# FeatherWing_for_MESH.net
KiCad netlist of a schematic drawn in EAGLE
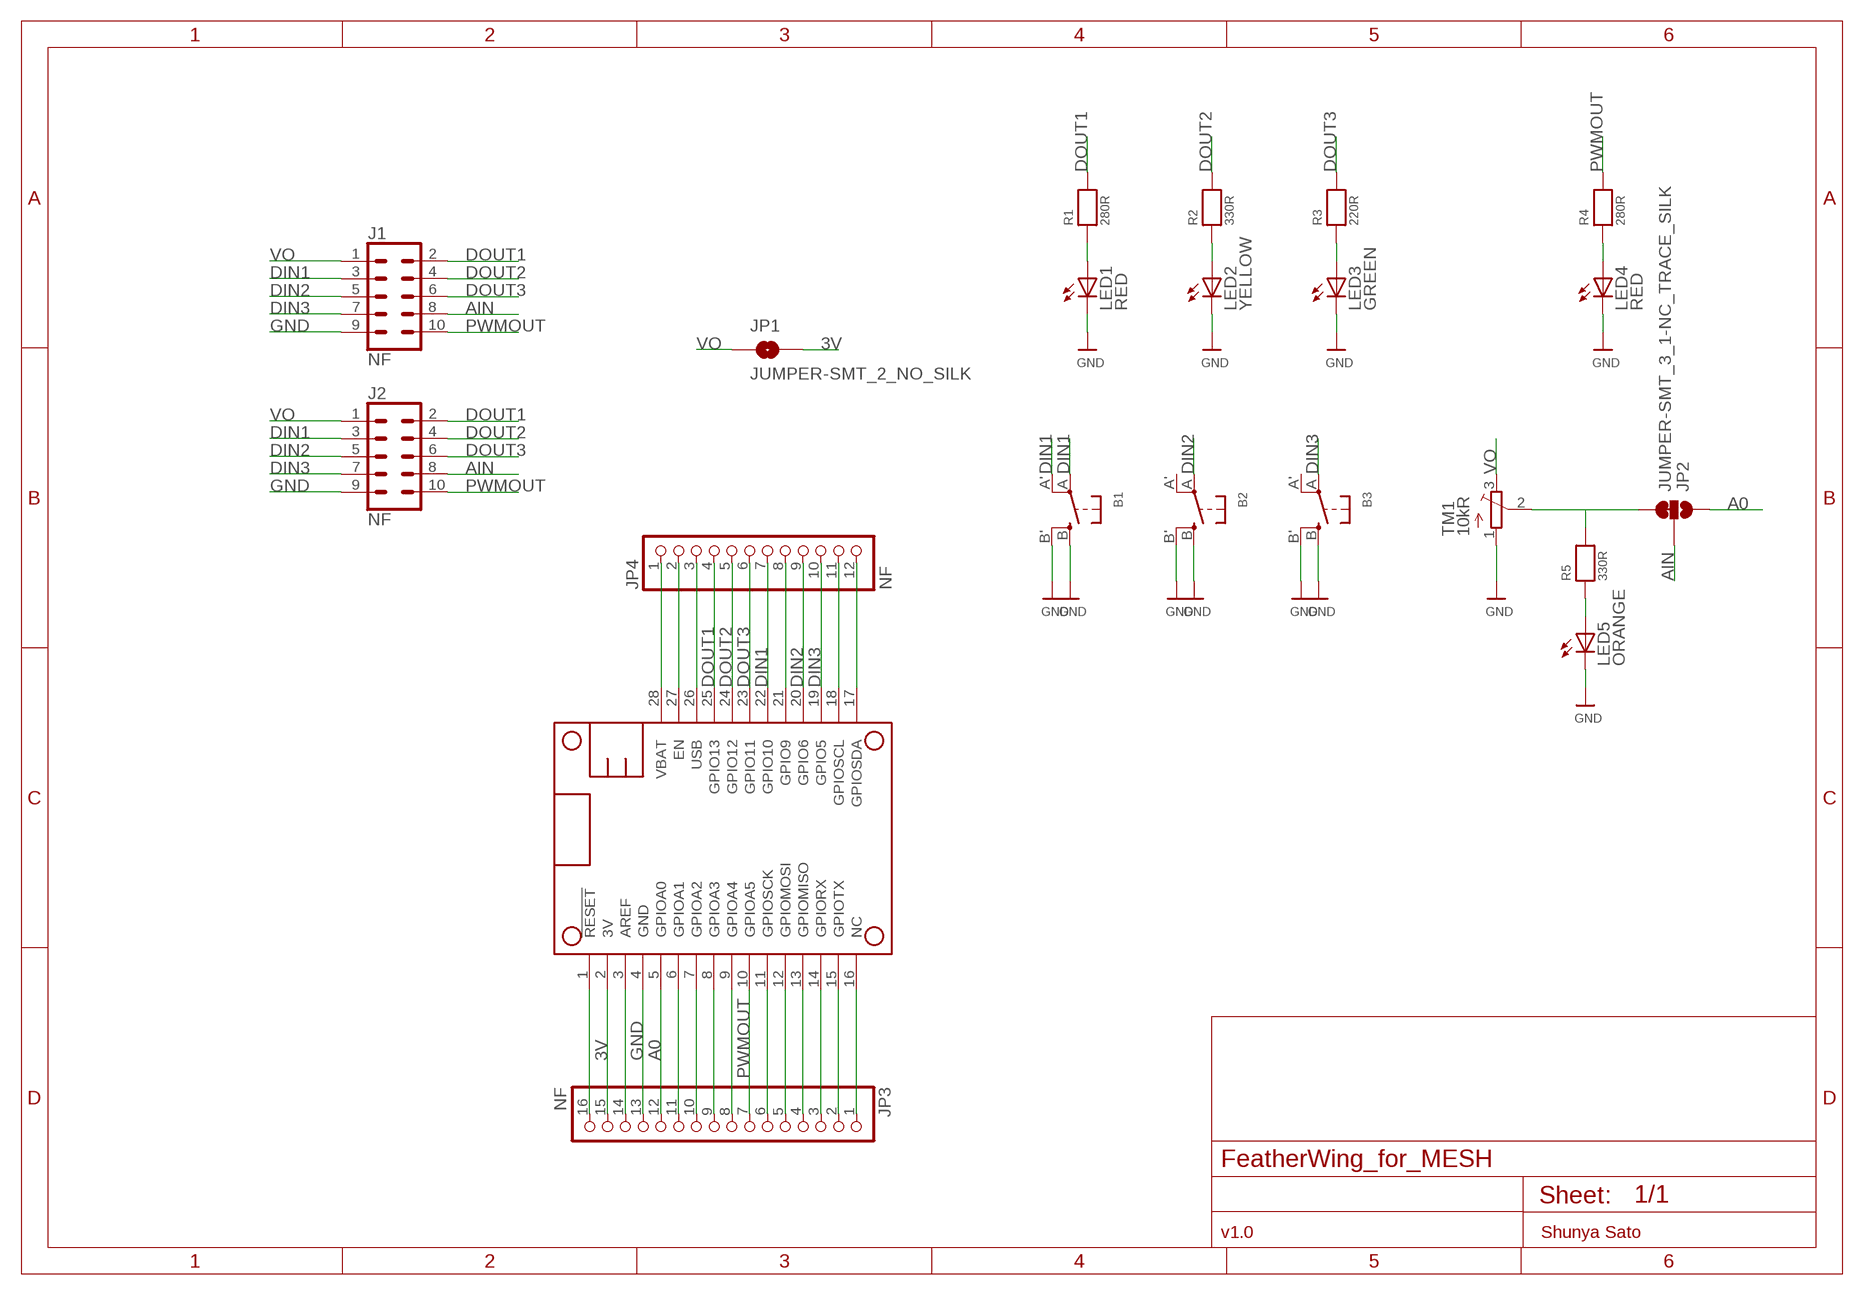
[diagram p0: schematic, sheet 1]

(export (version "E")
  (design (tool "Eeschema 10.0.6"))
  (components
    (comp (ref "B1")
      (value "SWITCH_TACT_SMT4.6X2.8")
      (footprint "eagle-import:BTN_KMR2_4.6X2.8")
      (libsource (lib "eagle-import") (part "SWITCH_TACT_SMT4.6X2.8"))
    )
    (comp (ref "B2")
      (value "SWITCH_TACT_SMT4.6X2.8")
      (footprint "eagle-import:BTN_KMR2_4.6X2.8")
      (libsource (lib "eagle-import") (part "SWITCH_TACT_SMT4.6X2.8"))
    )
    (comp (ref "B3")
      (value "SWITCH_TACT_SMT4.6X2.8")
      (footprint "eagle-import:BTN_KMR2_4.6X2.8")
      (libsource (lib "eagle-import") (part "SWITCH_TACT_SMT4.6X2.8"))
    )
    (comp (ref "J1")
      (value "NF")
      (footprint "eagle-import:2X5_NOSILK")
      (libsource (lib "eagle-import") (part "CONN_05X2NO_SILK"))
    )
    (comp (ref "J2")
      (value "NF")
      (footprint "eagle-import:2X5_NOSILK")
      (libsource (lib "eagle-import") (part "CONN_05X2NO_SILK"))
    )
    (comp (ref "JP1")
      (value "JUMPER-SMT_2_NO_SILK")
      (footprint "eagle-import:SMT-JUMPER_2_NO_SILK")
      (libsource (lib "eagle-import") (part "JUMPER-SMT_2_NO_SILK"))
    )
    (comp (ref "JP2")
      (value "JUMPER-SMT_3_1-NC_TRACE_SILK")
      (footprint "eagle-import:SMT-JUMPER_3_1-NC_TRACE_SILK")
      (libsource (lib "eagle-import") (part "JUMPER-SMT_3_1-NC_TRACE_SILK"))
    )
    (comp (ref "JP3")
      (value "NF")
      (footprint "eagle-import:1X16_ROUND_76MIL")
      (libsource (lib "eagle-import") (part "HEADER-1X16_76MIL"))
    )
    (comp (ref "JP4")
      (value "NF")
      (footprint "eagle-import:1X12_ROUND_76MIL")
      (libsource (lib "eagle-import") (part "HEADER-1X1276MIL"))
    )
    (comp (ref "LED1")
      (value "RED")
      (footprint "eagle-import:CHIPLED_0805")
      (libsource (lib "eagle-import") (part "LEDCHIPLED_0805"))
    )
    (comp (ref "LED2")
      (value "YELLOW")
      (footprint "eagle-import:CHIPLED_0805")
      (libsource (lib "eagle-import") (part "LEDCHIPLED_0805"))
    )
    (comp (ref "LED3")
      (value "GREEN")
      (footprint "eagle-import:CHIPLED_0805")
      (libsource (lib "eagle-import") (part "LEDCHIPLED_0805"))
    )
    (comp (ref "LED4")
      (value "RED")
      (footprint "eagle-import:CHIPLED_0805")
      (libsource (lib "eagle-import") (part "LEDCHIPLED_0805"))
    )
    (comp (ref "LED5")
      (value "ORANGE")
      (footprint "eagle-import:CHIPLED_0805")
      (libsource (lib "eagle-import") (part "LEDCHIPLED_0805"))
    )
    (comp (ref "MS1")
      (value "FEATHERWING")
      (footprint "eagle-import:FEATHERWING")
      (libsource (lib "eagle-import") (part "FEATHERWING"))
    )
    (comp (ref "R1")
      (value "280R")
      (footprint "eagle-import:0805_NOTHERMALS")
      (libsource (lib "eagle-import") (part "RESISTOR0805_NOTHERMALS"))
    )
    (comp (ref "R2")
      (value "330R")
      (footprint "eagle-import:0805_NOTHERMALS")
      (libsource (lib "eagle-import") (part "RESISTOR0805_NOTHERMALS"))
    )
    (comp (ref "R3")
      (value "220R")
      (footprint "eagle-import:0805_NOTHERMALS")
      (libsource (lib "eagle-import") (part "RESISTOR0805_NOTHERMALS"))
    )
    (comp (ref "R4")
      (value "280R")
      (footprint "eagle-import:0805_NOTHERMALS")
      (libsource (lib "eagle-import") (part "RESISTOR0805_NOTHERMALS"))
    )
    (comp (ref "R5")
      (value "330R")
      (footprint "eagle-import:0805_NOTHERMALS")
      (libsource (lib "eagle-import") (part "RESISTOR0805_NOTHERMALS"))
    )
    (comp (ref "TM1")
      (value "10kR")
      (footprint "eagle-import:TC33X")
      (libsource (lib "eagle-import") (part "TRIMPOTTC33X"))
    )
  )
  (nets
    (net (code "1") (name "/3V") (class "Default")
      (node (ref "JP1") (pin "2") (pinfunction "2_2") (pintype "passive"))
      (node (ref "JP3") (pin "15") (pinfunction "15_15") (pintype "passive"))
      (node (ref "MS1") (pin "2") (pinfunction "3V_2") (pintype "power_in"))
    )
    (net (code "2") (name "/A0") (class "Default")
      (node (ref "JP2") (pin "1") (pinfunction "1_1") (pintype "passive"))
      (node (ref "JP3") (pin "12") (pinfunction "12_12") (pintype "passive"))
      (node (ref "MS1") (pin "5") (pinfunction "GPIOA0_5") (pintype "bidirectional"))
    )
    (net (code "3") (name "/AIN") (class "Default")
      (node (ref "J1") (pin "8") (pinfunction "8_8") (pintype "passive"))
      (node (ref "J2") (pin "8") (pinfunction "8_8") (pintype "passive"))
      (node (ref "JP2") (pin "2") (pinfunction "2_2") (pintype "passive"))
    )
    (net (code "4") (name "/DIN1") (class "Default")
      (node (ref "B1") (pin "A") (pinfunction "P_A") (pintype "passive"))
      (node (ref "B1") (pin "A'") (pinfunction "P1_A'") (pintype "passive"))
      (node (ref "J1") (pin "3") (pinfunction "3_3") (pintype "passive"))
      (node (ref "J2") (pin "3") (pinfunction "3_3") (pintype "passive"))
      (node (ref "JP4") (pin "7") (pinfunction "7_7") (pintype "passive"))
      (node (ref "MS1") (pin "22") (pinfunction "GPIO10_22") (pintype "bidirectional"))
    )
    (net (code "5") (name "/DIN2") (class "Default")
      (node (ref "B2") (pin "A") (pinfunction "P_A") (pintype "passive"))
      (node (ref "J1") (pin "5") (pinfunction "5_5") (pintype "passive"))
      (node (ref "J2") (pin "5") (pinfunction "5_5") (pintype "passive"))
      (node (ref "JP4") (pin "9") (pinfunction "9_9") (pintype "passive"))
      (node (ref "MS1") (pin "20") (pinfunction "GPIO6_20") (pintype "bidirectional"))
    )
    (net (code "6") (name "/DIN3") (class "Default")
      (node (ref "B3") (pin "A") (pinfunction "P_A") (pintype "passive"))
      (node (ref "J1") (pin "7") (pinfunction "7_7") (pintype "passive"))
      (node (ref "J2") (pin "7") (pinfunction "7_7") (pintype "passive"))
      (node (ref "JP4") (pin "10") (pinfunction "10_10") (pintype "passive"))
      (node (ref "MS1") (pin "19") (pinfunction "GPIO5_19") (pintype "bidirectional"))
    )
    (net (code "7") (name "/DOUT1") (class "Default")
      (node (ref "J1") (pin "2") (pinfunction "2_2") (pintype "passive"))
      (node (ref "J2") (pin "2") (pinfunction "2_2") (pintype "passive"))
      (node (ref "JP4") (pin "4") (pinfunction "4_4") (pintype "passive"))
      (node (ref "MS1") (pin "25") (pinfunction "GPIO13_25") (pintype "bidirectional"))
      (node (ref "R1") (pin "2") (pinfunction "2_2") (pintype "passive"))
    )
    (net (code "8") (name "/DOUT2") (class "Default")
      (node (ref "J1") (pin "4") (pinfunction "4_4") (pintype "passive"))
      (node (ref "J2") (pin "4") (pinfunction "4_4") (pintype "passive"))
      (node (ref "JP4") (pin "5") (pinfunction "5_5") (pintype "passive"))
      (node (ref "MS1") (pin "24") (pinfunction "GPIO12_24") (pintype "bidirectional"))
      (node (ref "R2") (pin "2") (pinfunction "2_2") (pintype "passive"))
    )
    (net (code "9") (name "/DOUT3") (class "Default")
      (node (ref "J1") (pin "6") (pinfunction "6_6") (pintype "passive"))
      (node (ref "J2") (pin "6") (pinfunction "6_6") (pintype "passive"))
      (node (ref "JP4") (pin "6") (pinfunction "6_6") (pintype "passive"))
      (node (ref "MS1") (pin "23") (pinfunction "GPIO11_23") (pintype "bidirectional"))
      (node (ref "R3") (pin "2") (pinfunction "2_2") (pintype "passive"))
    )
    (net (code "10") (name "/PWMOUT") (class "Default")
      (node (ref "J1") (pin "10") (pinfunction "10_10") (pintype "passive"))
      (node (ref "J2") (pin "10") (pinfunction "10_10") (pintype "passive"))
      (node (ref "JP3") (pin "7") (pinfunction "7_7") (pintype "passive"))
      (node (ref "MS1") (pin "10") (pinfunction "GPIOA5_10") (pintype "bidirectional"))
      (node (ref "R4") (pin "2") (pinfunction "2_2") (pintype "passive"))
    )
    (net (code "11") (name "/VO") (class "Default")
      (node (ref "J1") (pin "1") (pinfunction "1_1") (pintype "passive"))
      (node (ref "J2") (pin "1") (pinfunction "1_1") (pintype "passive"))
      (node (ref "JP1") (pin "1") (pinfunction "1_1") (pintype "passive"))
      (node (ref "TM1") (pin "3") (pinfunction "E_3") (pintype "passive"))
    )
    (net (code "12") (name "GND") (class "Default")
      (node (ref "B1") (pin "B") (pinfunction "S_B") (pintype "passive"))
      (node (ref "B1") (pin "B'") (pinfunction "S1_B'") (pintype "passive"))
      (node (ref "B2") (pin "B") (pinfunction "S_B") (pintype "passive"))
      (node (ref "B2") (pin "B'") (pinfunction "S1_B'") (pintype "passive"))
      (node (ref "B3") (pin "B") (pinfunction "S_B") (pintype "passive"))
      (node (ref "B3") (pin "B'") (pinfunction "S1_B'") (pintype "passive"))
      (node (ref "J1") (pin "9") (pinfunction "9_9") (pintype "passive"))
      (node (ref "J2") (pin "9") (pinfunction "9_9") (pintype "passive"))
      (node (ref "JP3") (pin "13") (pinfunction "13_13") (pintype "passive"))
      (node (ref "LED1") (pin "C") (pinfunction "C_C") (pintype "passive"))
      (node (ref "LED2") (pin "C") (pinfunction "C_C") (pintype "passive"))
      (node (ref "LED3") (pin "C") (pinfunction "C_C") (pintype "passive"))
      (node (ref "LED4") (pin "C") (pinfunction "C_C") (pintype "passive"))
      (node (ref "LED5") (pin "C") (pinfunction "C_C") (pintype "passive"))
      (node (ref "MS1") (pin "4") (pinfunction "GND_4") (pintype "power_in"))
      (node (ref "TM1") (pin "1") (pinfunction "A_1") (pintype "passive"))
    )
    (net (code "13") (name "Net-(LED1-PadA)") (class "Default")
      (node (ref "LED1") (pin "A") (pinfunction "A_A") (pintype "passive"))
      (node (ref "R1") (pin "1") (pinfunction "1_1") (pintype "passive"))
    )
    (net (code "14") (name "Net-(LED2-PadA)") (class "Default")
      (node (ref "LED2") (pin "A") (pinfunction "A_A") (pintype "passive"))
      (node (ref "R2") (pin "1") (pinfunction "1_1") (pintype "passive"))
    )
    (net (code "15") (name "Net-(LED3-PadA)") (class "Default")
      (node (ref "LED3") (pin "A") (pinfunction "A_A") (pintype "passive"))
      (node (ref "R3") (pin "1") (pinfunction "1_1") (pintype "passive"))
    )
    (net (code "16") (name "Net-(LED4-PadA)") (class "Default")
      (node (ref "LED4") (pin "A") (pinfunction "A_A") (pintype "passive"))
      (node (ref "R4") (pin "1") (pinfunction "1_1") (pintype "passive"))
    )
    (net (code "17") (name "Net-(LED5-PadA)") (class "Default")
      (node (ref "LED5") (pin "A") (pinfunction "A_A") (pintype "passive"))
      (node (ref "R5") (pin "1") (pinfunction "1_1") (pintype "passive"))
    )
    (net (code "18") (name "Net-(MS1-AREF)") (class "Default")
      (node (ref "JP3") (pin "14") (pinfunction "14_14") (pintype "passive"))
      (node (ref "MS1") (pin "3") (pinfunction "AREF_3") (pintype "passive"))
    )
    (net (code "19") (name "Net-(MS1-EN)") (class "Default")
      (node (ref "JP4") (pin "2") (pinfunction "2_2") (pintype "passive"))
      (node (ref "MS1") (pin "27") (pinfunction "EN_27") (pintype "passive"))
    )
    (net (code "20") (name "Net-(MS1-GPIO9)") (class "Default")
      (node (ref "JP4") (pin "8") (pinfunction "8_8") (pintype "passive"))
      (node (ref "MS1") (pin "21") (pinfunction "GPIO9_21") (pintype "bidirectional"))
    )
    (net (code "21") (name "Net-(MS1-GPIOA1)") (class "Default")
      (node (ref "JP3") (pin "11") (pinfunction "11_11") (pintype "passive"))
      (node (ref "MS1") (pin "6") (pinfunction "GPIOA1_6") (pintype "bidirectional"))
    )
    (net (code "22") (name "Net-(MS1-GPIOA2)") (class "Default")
      (node (ref "JP3") (pin "10") (pinfunction "10_10") (pintype "passive"))
      (node (ref "MS1") (pin "7") (pinfunction "GPIOA2_7") (pintype "bidirectional"))
    )
    (net (code "23") (name "Net-(MS1-GPIOA3)") (class "Default")
      (node (ref "JP3") (pin "9") (pinfunction "9_9") (pintype "passive"))
      (node (ref "MS1") (pin "8") (pinfunction "GPIOA3_8") (pintype "bidirectional"))
    )
    (net (code "24") (name "Net-(MS1-GPIOA4)") (class "Default")
      (node (ref "JP3") (pin "8") (pinfunction "8_8") (pintype "passive"))
      (node (ref "MS1") (pin "9") (pinfunction "GPIOA4_9") (pintype "bidirectional"))
    )
    (net (code "25") (name "Net-(MS1-GPIOMISO)") (class "Default")
      (node (ref "JP3") (pin "4") (pinfunction "4_4") (pintype "passive"))
      (node (ref "MS1") (pin "13") (pinfunction "GPIOMISO_13") (pintype "bidirectional"))
    )
    (net (code "26") (name "Net-(MS1-GPIOMOSI)") (class "Default")
      (node (ref "JP3") (pin "5") (pinfunction "5_5") (pintype "passive"))
      (node (ref "MS1") (pin "12") (pinfunction "GPIOMOSI_12") (pintype "bidirectional"))
    )
    (net (code "27") (name "Net-(MS1-GPIORX)") (class "Default")
      (node (ref "JP3") (pin "3") (pinfunction "3_3") (pintype "passive"))
      (node (ref "MS1") (pin "14") (pinfunction "GPIORX_14") (pintype "bidirectional"))
    )
    (net (code "28") (name "Net-(MS1-GPIOSCK)") (class "Default")
      (node (ref "JP3") (pin "6") (pinfunction "6_6") (pintype "passive"))
      (node (ref "MS1") (pin "11") (pinfunction "GPIOSCK_11") (pintype "bidirectional"))
    )
    (net (code "29") (name "Net-(MS1-GPIOSCL)") (class "Default")
      (node (ref "JP4") (pin "11") (pinfunction "11_11") (pintype "passive"))
      (node (ref "MS1") (pin "18") (pinfunction "GPIOSCL_18") (pintype "bidirectional"))
    )
    (net (code "30") (name "Net-(MS1-GPIOSDA)") (class "Default")
      (node (ref "JP4") (pin "12") (pinfunction "12_12") (pintype "passive"))
      (node (ref "MS1") (pin "17") (pinfunction "GPIOSDA_17") (pintype "bidirectional"))
    )
    (net (code "31") (name "Net-(MS1-GPIOTX)") (class "Default")
      (node (ref "JP3") (pin "2") (pinfunction "2_2") (pintype "passive"))
      (node (ref "MS1") (pin "15") (pinfunction "GPIOTX_15") (pintype "bidirectional"))
    )
    (net (code "32") (name "Net-(MS1-NC)") (class "Default")
      (node (ref "JP3") (pin "1") (pinfunction "1_1") (pintype "passive"))
      (node (ref "MS1") (pin "16") (pinfunction "NC_16") (pintype "passive"))
    )
    (net (code "33") (name "Net-(MS1-USB)") (class "Default")
      (node (ref "JP4") (pin "3") (pinfunction "3_3") (pintype "passive"))
      (node (ref "MS1") (pin "26") (pinfunction "USB_26") (pintype "power_in"))
    )
    (net (code "34") (name "Net-(MS1-VBAT)") (class "Default")
      (node (ref "JP4") (pin "1") (pinfunction "1_1") (pintype "passive"))
      (node (ref "MS1") (pin "28") (pinfunction "VBAT_28") (pintype "power_in"))
    )
    (net (code "35") (name "Net-(MS1-~{RESET})") (class "Default")
      (node (ref "JP3") (pin "16") (pinfunction "16_16") (pintype "passive"))
      (node (ref "MS1") (pin "1") (pinfunction "~{RESET}_1") (pintype "input"))
    )
    (net (code "36") (name "Net-(TM1-S)") (class "Default")
      (node (ref "JP2") (pin "3") (pinfunction "3_3") (pintype "passive"))
      (node (ref "R5") (pin "2") (pinfunction "2_2") (pintype "passive"))
      (node (ref "TM1") (pin "2") (pinfunction "S_2") (pintype "passive"))
    )
    (net (code "37") (name "unconnected-(B2-P1-PadA')") (class "Default")
      (node (ref "B2") (pin "A'") (pinfunction "P1_A'") (pintype "passive"))
    )
    (net (code "38") (name "unconnected-(B3-P1-PadA')") (class "Default")
      (node (ref "B3") (pin "A'") (pinfunction "P1_A'") (pintype "passive"))
    )
  )
)
